# filter2.net
KiCad netlist of a schematic drawn in EAGLE
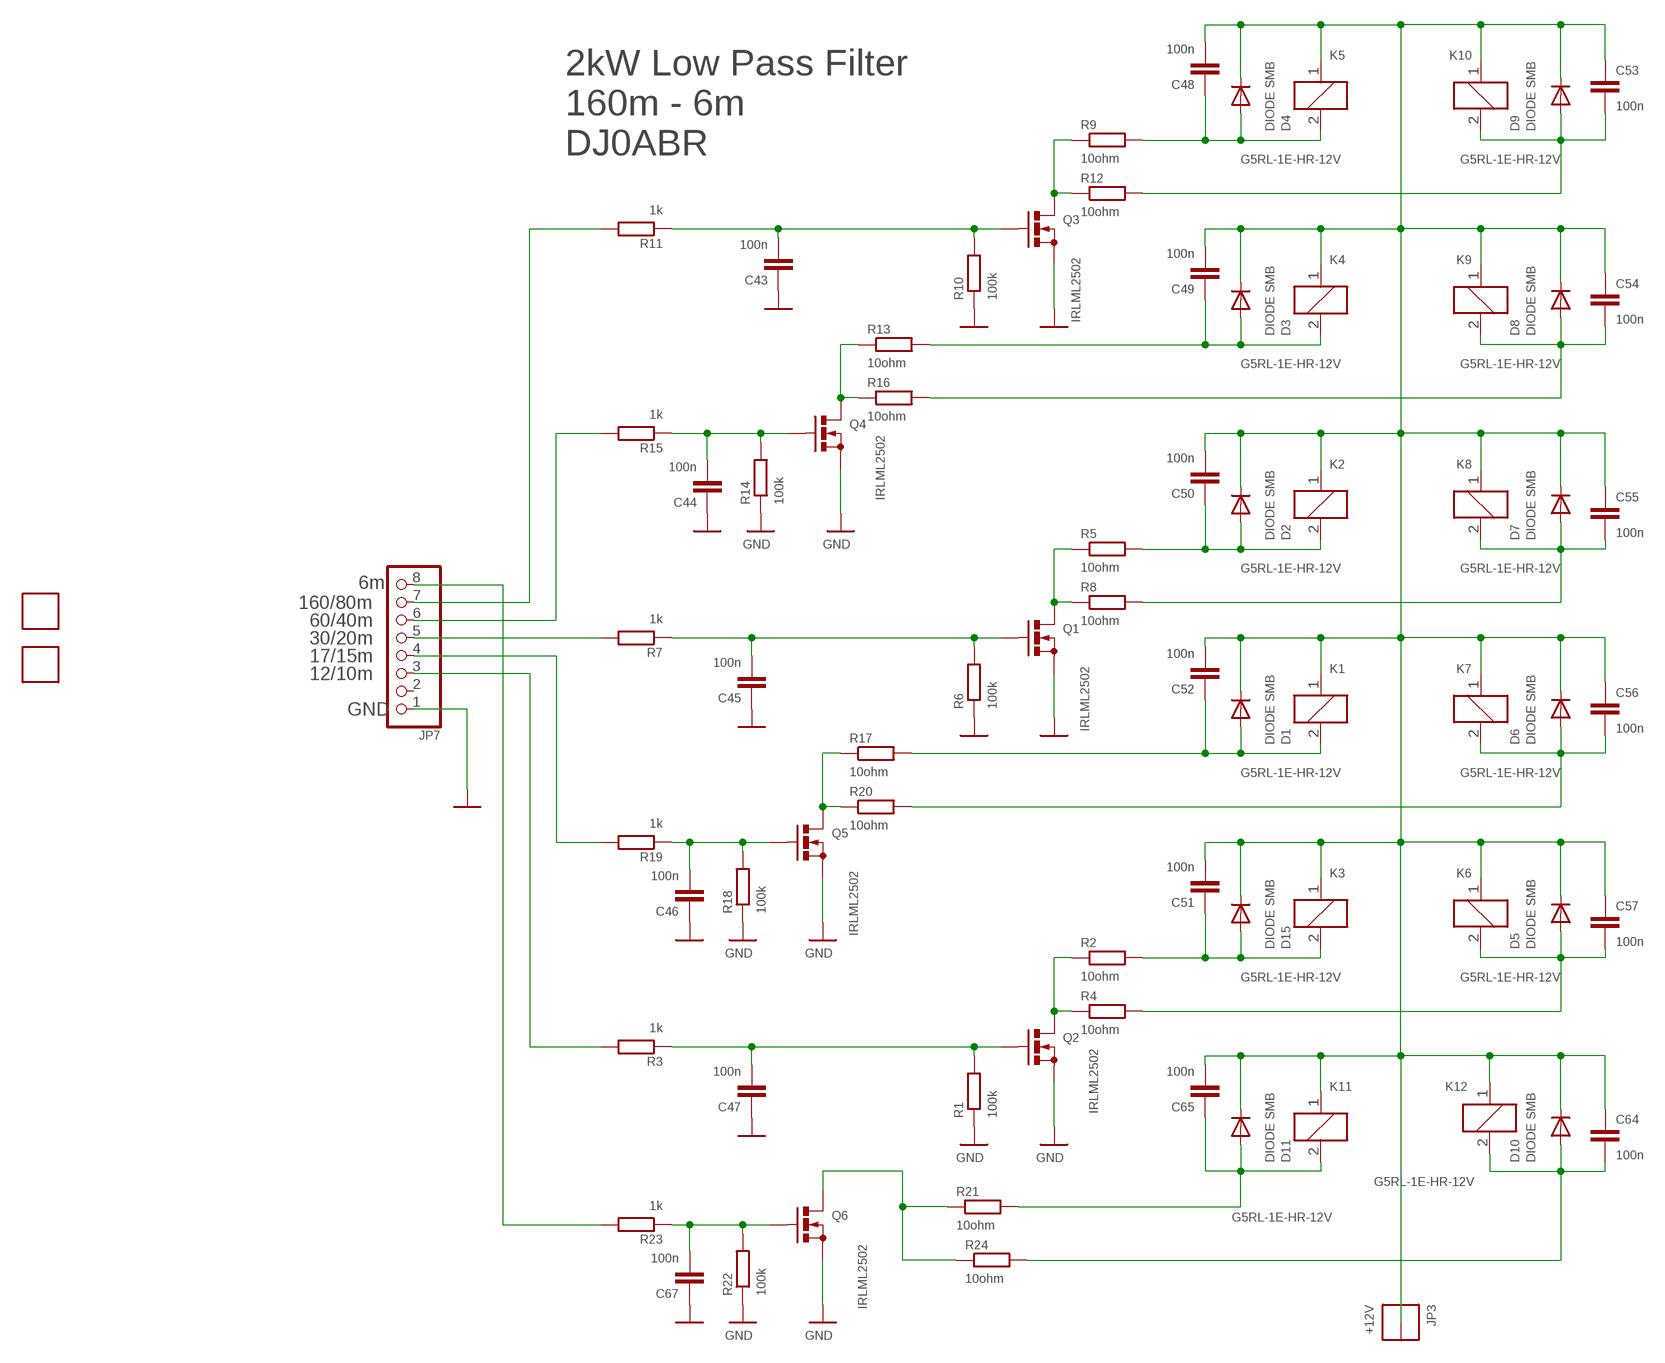
[diagram p0: schematic, sheet 1, part 1 of 2]
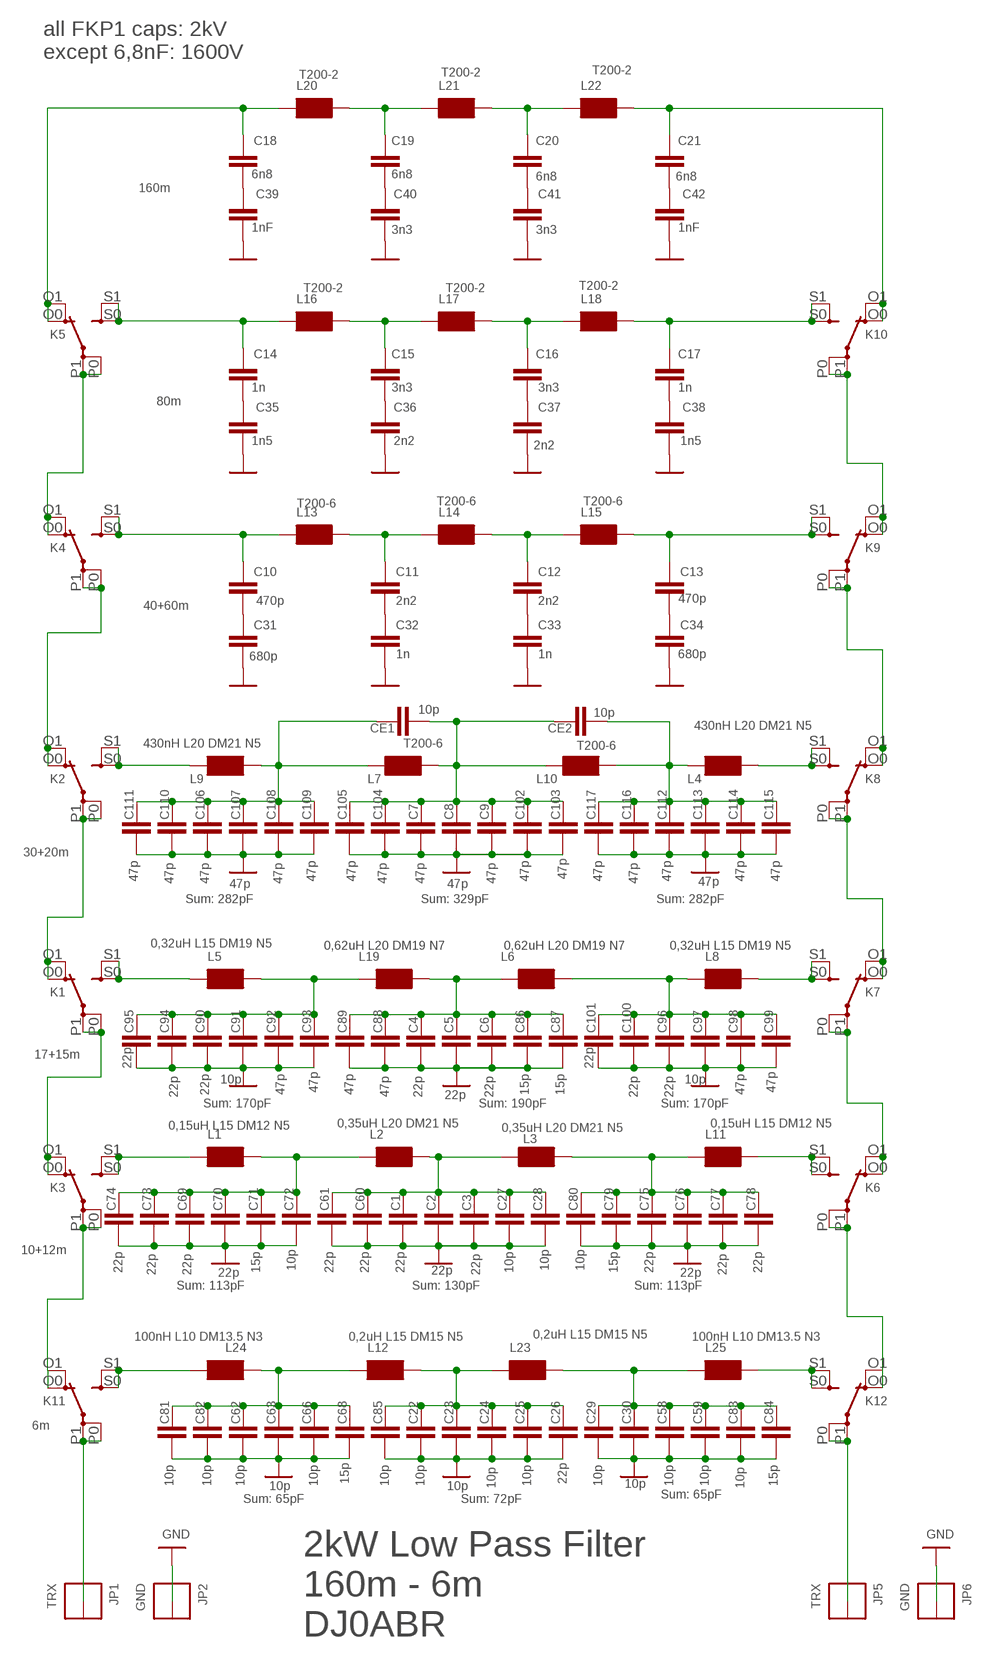
[diagram p1: schematic, sheet 1, part 2 of 2]

(export (version "E")
  (design (tool "Eeschema 10.0.6"))
  (components
    (comp (ref "C1")
      (value "22p")
      (footprint "eagle-import:C1812K")
      (libsource (lib "eagle-import") (part "C-EUC1812K"))
    )
    (comp (ref "C2")
      (value "22p")
      (footprint "eagle-import:C1812K")
      (libsource (lib "eagle-import") (part "C-EUC1812K"))
    )
    (comp (ref "C3")
      (value "22p")
      (footprint "eagle-import:C1812K")
      (libsource (lib "eagle-import") (part "C-EUC1812K"))
    )
    (comp (ref "C4")
      (value "22p")
      (footprint "eagle-import:C1812K")
      (libsource (lib "eagle-import") (part "C-EUC1812K"))
    )
    (comp (ref "C5")
      (value "22p")
      (footprint "eagle-import:C1812K")
      (libsource (lib "eagle-import") (part "C-EUC1812K"))
    )
    (comp (ref "C6")
      (value "22p")
      (footprint "eagle-import:C1812K")
      (libsource (lib "eagle-import") (part "C-EUC1812K"))
    )
    (comp (ref "C7")
      (value "47p")
      (footprint "eagle-import:C1812K")
      (libsource (lib "eagle-import") (part "C-EUC1812K"))
    )
    (comp (ref "C8")
      (value "47p")
      (footprint "eagle-import:C1812K")
      (libsource (lib "eagle-import") (part "C-EUC1812K"))
    )
    (comp (ref "C9")
      (value "47p")
      (footprint "eagle-import:C1812K")
      (libsource (lib "eagle-import") (part "C-EUC1812K"))
    )
    (comp (ref "C10")
      (value "470p")
      (footprint "eagle-import:C150-064X183")
      (libsource (lib "eagle-import") (part "C-EU150-064X183"))
    )
    (comp (ref "C11")
      (value "2n2")
      (footprint "eagle-import:C225-074X268")
      (libsource (lib "eagle-import") (part "C-EU225-074X268"))
    )
    (comp (ref "C12")
      (value "2n2")
      (footprint "eagle-import:C225-074X268")
      (libsource (lib "eagle-import") (part "C-EU225-074X268"))
    )
    (comp (ref "C13")
      (value "470p")
      (footprint "eagle-import:C150-064X183")
      (libsource (lib "eagle-import") (part "C-EU150-064X183"))
    )
    (comp (ref "C14")
      (value "1n")
      (footprint "eagle-import:C225-062X268")
      (libsource (lib "eagle-import") (part "C-EU225-062X268"))
    )
    (comp (ref "C15")
      (value "3n3")
      (footprint "eagle-import:C225-074X268")
      (libsource (lib "eagle-import") (part "C-EU225-074X268"))
    )
    (comp (ref "C16")
      (value "3n3")
      (footprint "eagle-import:C225-074X268")
      (libsource (lib "eagle-import") (part "C-EU225-074X268"))
    )
    (comp (ref "C17")
      (value "1n")
      (footprint "eagle-import:C225-062X268")
      (libsource (lib "eagle-import") (part "C-EU225-062X268"))
    )
    (comp (ref "C18")
      (value "6n8")
      (footprint "eagle-import:C225-074X268")
      (libsource (lib "eagle-import") (part "C-EU225-074X268"))
    )
    (comp (ref "C19")
      (value "6n8")
      (footprint "eagle-import:C225-074X268")
      (libsource (lib "eagle-import") (part "C-EU225-074X268"))
    )
    (comp (ref "C20")
      (value "6n8")
      (footprint "eagle-import:C225-074X268")
      (libsource (lib "eagle-import") (part "C-EU225-074X268"))
    )
    (comp (ref "C21")
      (value "6n8")
      (footprint "eagle-import:C225-074X268")
      (libsource (lib "eagle-import") (part "C-EU225-074X268"))
    )
    (comp (ref "C22")
      (value "10p")
      (footprint "eagle-import:C1812K")
      (libsource (lib "eagle-import") (part "C-EUC1812K"))
    )
    (comp (ref "C23")
      (value "10p")
      (footprint "eagle-import:C1812K")
      (libsource (lib "eagle-import") (part "C-EUC1812K"))
    )
    (comp (ref "C24")
      (value "10p")
      (footprint "eagle-import:C1812K")
      (libsource (lib "eagle-import") (part "C-EUC1812K"))
    )
    (comp (ref "C25")
      (value "10p")
      (footprint "eagle-import:C1812K")
      (libsource (lib "eagle-import") (part "C-EUC1812K"))
    )
    (comp (ref "C26")
      (value "22p")
      (footprint "eagle-import:C1812K")
      (libsource (lib "eagle-import") (part "C-EUC1812K"))
    )
    (comp (ref "C27")
      (value "10p")
      (footprint "eagle-import:C1812K")
      (libsource (lib "eagle-import") (part "C-EUC1812K"))
    )
    (comp (ref "C28")
      (value "10p")
      (footprint "eagle-import:C1812K")
      (libsource (lib "eagle-import") (part "C-EUC1812K"))
    )
    (comp (ref "C29")
      (value "10p")
      (footprint "eagle-import:C1812K")
      (libsource (lib "eagle-import") (part "C-EUC1812K"))
    )
    (comp (ref "C30")
      (value "10p")
      (footprint "eagle-import:C1812K")
      (libsource (lib "eagle-import") (part "C-EUC1812K"))
    )
    (comp (ref "C31")
      (value "680p")
      (footprint "eagle-import:C150-064X183")
      (libsource (lib "eagle-import") (part "C-EU150-064X183"))
    )
    (comp (ref "C32")
      (value "1n")
      (footprint "eagle-import:C225-062X268")
      (libsource (lib "eagle-import") (part "C-EU225-062X268"))
    )
    (comp (ref "C33")
      (value "1n")
      (footprint "eagle-import:C225-062X268")
      (libsource (lib "eagle-import") (part "C-EU225-062X268"))
    )
    (comp (ref "C34")
      (value "680p")
      (footprint "eagle-import:C150-064X183")
      (libsource (lib "eagle-import") (part "C-EU150-064X183"))
    )
    (comp (ref "C35")
      (value "1n5")
      (footprint "eagle-import:C225-074X268")
      (libsource (lib "eagle-import") (part "C-EU225-074X268"))
    )
    (comp (ref "C36")
      (value "2n2")
      (footprint "eagle-import:C225-074X268")
      (libsource (lib "eagle-import") (part "C-EU225-074X268"))
    )
    (comp (ref "C37")
      (value "2n2")
      (footprint "eagle-import:C225-074X268")
      (libsource (lib "eagle-import") (part "C-EU225-074X268"))
    )
    (comp (ref "C38")
      (value "1n5")
      (footprint "eagle-import:C225-074X268")
      (libsource (lib "eagle-import") (part "C-EU225-074X268"))
    )
    (comp (ref "C39")
      (value "1nF")
      (footprint "eagle-import:C225-074X268")
      (libsource (lib "eagle-import") (part "C-EU225-074X268"))
    )
    (comp (ref "C40")
      (value "3n3")
      (footprint "eagle-import:C225-087X268")
      (libsource (lib "eagle-import") (part "C-EU225-087X268"))
    )
    (comp (ref "C41")
      (value "3n3")
      (footprint "eagle-import:C225-087X268")
      (libsource (lib "eagle-import") (part "C-EU225-087X268"))
    )
    (comp (ref "C42")
      (value "1nF")
      (footprint "eagle-import:C225-074X268")
      (libsource (lib "eagle-import") (part "C-EU225-074X268"))
    )
    (comp (ref "C43")
      (value "100n")
      (footprint "eagle-import:C0603K")
      (libsource (lib "eagle-import") (part "C-EUC0603K"))
    )
    (comp (ref "C44")
      (value "100n")
      (footprint "eagle-import:C0603K")
      (libsource (lib "eagle-import") (part "C-EUC0603K"))
    )
    (comp (ref "C45")
      (value "100n")
      (footprint "eagle-import:C0603K")
      (libsource (lib "eagle-import") (part "C-EUC0603K"))
    )
    (comp (ref "C46")
      (value "100n")
      (footprint "eagle-import:C0603K")
      (libsource (lib "eagle-import") (part "C-EUC0603K"))
    )
    (comp (ref "C47")
      (value "100n")
      (footprint "eagle-import:C0603K")
      (libsource (lib "eagle-import") (part "C-EUC0603K"))
    )
    (comp (ref "C48")
      (value "100n")
      (footprint "eagle-import:C0603K")
      (libsource (lib "eagle-import") (part "C-EUC0603K"))
    )
    (comp (ref "C49")
      (value "100n")
      (footprint "eagle-import:C0603K")
      (libsource (lib "eagle-import") (part "C-EUC0603K"))
    )
    (comp (ref "C50")
      (value "100n")
      (footprint "eagle-import:C0603K")
      (libsource (lib "eagle-import") (part "C-EUC0603K"))
    )
    (comp (ref "C51")
      (value "100n")
      (footprint "eagle-import:C0603K")
      (libsource (lib "eagle-import") (part "C-EUC0603K"))
    )
    (comp (ref "C52")
      (value "100n")
      (footprint "eagle-import:C0603K")
      (libsource (lib "eagle-import") (part "C-EUC0603K"))
    )
    (comp (ref "C53")
      (value "100n")
      (footprint "eagle-import:C0603K")
      (libsource (lib "eagle-import") (part "C-EUC0603K"))
    )
    (comp (ref "C54")
      (value "100n")
      (footprint "eagle-import:C0603K")
      (libsource (lib "eagle-import") (part "C-EUC0603K"))
    )
    (comp (ref "C55")
      (value "100n")
      (footprint "eagle-import:C0603K")
      (libsource (lib "eagle-import") (part "C-EUC0603K"))
    )
    (comp (ref "C56")
      (value "100n")
      (footprint "eagle-import:C0603K")
      (libsource (lib "eagle-import") (part "C-EUC0603K"))
    )
    (comp (ref "C57")
      (value "100n")
      (footprint "eagle-import:C0603K")
      (libsource (lib "eagle-import") (part "C-EUC0603K"))
    )
    (comp (ref "C58")
      (value "10p")
      (footprint "eagle-import:C1812K")
      (libsource (lib "eagle-import") (part "C-EUC1812K"))
    )
    (comp (ref "C59")
      (value "10p")
      (footprint "eagle-import:C1812K")
      (libsource (lib "eagle-import") (part "C-EUC1812K"))
    )
    (comp (ref "C60")
      (value "22p")
      (footprint "eagle-import:C1812K")
      (libsource (lib "eagle-import") (part "C-EUC1812K"))
    )
    (comp (ref "C61")
      (value "22p")
      (footprint "eagle-import:C1812K")
      (libsource (lib "eagle-import") (part "C-EUC1812K"))
    )
    (comp (ref "C62")
      (value "10p")
      (footprint "eagle-import:C1812K")
      (libsource (lib "eagle-import") (part "C-EUC1812K"))
    )
    (comp (ref "C63")
      (value "10p")
      (footprint "eagle-import:C1812K")
      (libsource (lib "eagle-import") (part "C-EUC1812K"))
    )
    (comp (ref "C64")
      (value "100n")
      (footprint "eagle-import:C0603K")
      (libsource (lib "eagle-import") (part "C-EUC0603K"))
    )
    (comp (ref "C65")
      (value "100n")
      (footprint "eagle-import:C0603K")
      (libsource (lib "eagle-import") (part "C-EUC0603K"))
    )
    (comp (ref "C66")
      (value "10p")
      (footprint "eagle-import:C1812K")
      (libsource (lib "eagle-import") (part "C-EUC1812K"))
    )
    (comp (ref "C67")
      (value "100n")
      (footprint "eagle-import:C0603K")
      (libsource (lib "eagle-import") (part "C-EUC0603K"))
    )
    (comp (ref "C68")
      (value "15p")
      (footprint "eagle-import:C1812K")
      (libsource (lib "eagle-import") (part "C-EUC1812K"))
    )
    (comp (ref "C69")
      (value "22p")
      (footprint "eagle-import:C1812K")
      (libsource (lib "eagle-import") (part "C-EUC1812K"))
    )
    (comp (ref "C70")
      (value "22p")
      (footprint "eagle-import:C1812K")
      (libsource (lib "eagle-import") (part "C-EUC1812K"))
    )
    (comp (ref "C71")
      (value "15p")
      (footprint "eagle-import:C1812K")
      (libsource (lib "eagle-import") (part "C-EUC1812K"))
    )
    (comp (ref "C72")
      (value "10p")
      (footprint "eagle-import:C1812K")
      (libsource (lib "eagle-import") (part "C-EUC1812K"))
    )
    (comp (ref "C73")
      (value "22p")
      (footprint "eagle-import:C1812K")
      (libsource (lib "eagle-import") (part "C-EUC1812K"))
    )
    (comp (ref "C74")
      (value "22p")
      (footprint "eagle-import:C1812K")
      (libsource (lib "eagle-import") (part "C-EUC1812K"))
    )
    (comp (ref "C75")
      (value "22p")
      (footprint "eagle-import:C1812K")
      (libsource (lib "eagle-import") (part "C-EUC1812K"))
    )
    (comp (ref "C76")
      (value "22p")
      (footprint "eagle-import:C1812K")
      (libsource (lib "eagle-import") (part "C-EUC1812K"))
    )
    (comp (ref "C77")
      (value "22p")
      (footprint "eagle-import:C1812K")
      (libsource (lib "eagle-import") (part "C-EUC1812K"))
    )
    (comp (ref "C78")
      (value "22p")
      (footprint "eagle-import:C1812K")
      (libsource (lib "eagle-import") (part "C-EUC1812K"))
    )
    (comp (ref "C79")
      (value "15p")
      (footprint "eagle-import:C1812K")
      (libsource (lib "eagle-import") (part "C-EUC1812K"))
    )
    (comp (ref "C80")
      (value "10p")
      (footprint "eagle-import:C1812K")
      (libsource (lib "eagle-import") (part "C-EUC1812K"))
    )
    (comp (ref "C81")
      (value "10p")
      (footprint "eagle-import:C1812K")
      (libsource (lib "eagle-import") (part "C-EUC1812K"))
    )
    (comp (ref "C82")
      (value "10p")
      (footprint "eagle-import:C1812K")
      (libsource (lib "eagle-import") (part "C-EUC1812K"))
    )
    (comp (ref "C83")
      (value "10p")
      (footprint "eagle-import:C1812K")
      (libsource (lib "eagle-import") (part "C-EUC1812K"))
    )
    (comp (ref "C84")
      (value "15p")
      (footprint "eagle-import:C1812K")
      (libsource (lib "eagle-import") (part "C-EUC1812K"))
    )
    (comp (ref "C85")
      (value "10p")
      (footprint "eagle-import:C1812K")
      (libsource (lib "eagle-import") (part "C-EUC1812K"))
    )
    (comp (ref "C86")
      (value "15p")
      (footprint "eagle-import:C1812K")
      (libsource (lib "eagle-import") (part "C-EUC1812K"))
    )
    (comp (ref "C87")
      (value "15p")
      (footprint "eagle-import:C1812K")
      (libsource (lib "eagle-import") (part "C-EUC1812K"))
    )
    (comp (ref "C88")
      (value "47p")
      (footprint "eagle-import:C1812K")
      (libsource (lib "eagle-import") (part "C-EUC1812K"))
    )
    (comp (ref "C89")
      (value "47p")
      (footprint "eagle-import:C1812K")
      (libsource (lib "eagle-import") (part "C-EUC1812K"))
    )
    (comp (ref "C90")
      (value "22p")
      (footprint "eagle-import:C1812K")
      (libsource (lib "eagle-import") (part "C-EUC1812K"))
    )
    (comp (ref "C91")
      (value "10p")
      (footprint "eagle-import:C1812K")
      (libsource (lib "eagle-import") (part "C-EUC1812K"))
    )
    (comp (ref "C92")
      (value "47p")
      (footprint "eagle-import:C1812K")
      (libsource (lib "eagle-import") (part "C-EUC1812K"))
    )
    (comp (ref "C93")
      (value "47p")
      (footprint "eagle-import:C1812K")
      (libsource (lib "eagle-import") (part "C-EUC1812K"))
    )
    (comp (ref "C94")
      (value "22p")
      (footprint "eagle-import:C1812K")
      (libsource (lib "eagle-import") (part "C-EUC1812K"))
    )
    (comp (ref "C95")
      (value "22p")
      (footprint "eagle-import:C1812K")
      (libsource (lib "eagle-import") (part "C-EUC1812K"))
    )
    (comp (ref "C96")
      (value "22p")
      (footprint "eagle-import:C1812K")
      (libsource (lib "eagle-import") (part "C-EUC1812K"))
    )
    (comp (ref "C97")
      (value "10p")
      (footprint "eagle-import:C1812K")
      (libsource (lib "eagle-import") (part "C-EUC1812K"))
    )
    (comp (ref "C98")
      (value "47p")
      (footprint "eagle-import:C1812K")
      (libsource (lib "eagle-import") (part "C-EUC1812K"))
    )
    (comp (ref "C99")
      (value "47p")
      (footprint "eagle-import:C1812K")
      (libsource (lib "eagle-import") (part "C-EUC1812K"))
    )
    (comp (ref "C100")
      (value "22p")
      (footprint "eagle-import:C1812K")
      (libsource (lib "eagle-import") (part "C-EUC1812K"))
    )
    (comp (ref "C101")
      (value "22p")
      (footprint "eagle-import:C1812K")
      (libsource (lib "eagle-import") (part "C-EUC1812K"))
    )
    (comp (ref "C102")
      (value "47p")
      (footprint "eagle-import:C1812K")
      (libsource (lib "eagle-import") (part "C-EUC1812K"))
    )
    (comp (ref "C103")
      (value "47p")
      (footprint "eagle-import:C1812K")
      (libsource (lib "eagle-import") (part "C-EUC1812K"))
    )
    (comp (ref "C104")
      (value "47p")
      (footprint "eagle-import:C1812K")
      (libsource (lib "eagle-import") (part "C-EUC1812K"))
    )
    (comp (ref "C105")
      (value "47p")
      (footprint "eagle-import:C1812K")
      (libsource (lib "eagle-import") (part "C-EUC1812K"))
    )
    (comp (ref "C106")
      (value "47p")
      (footprint "eagle-import:C1812K")
      (libsource (lib "eagle-import") (part "C-EUC1812K"))
    )
    (comp (ref "C107")
      (value "47p")
      (footprint "eagle-import:C1812K")
      (libsource (lib "eagle-import") (part "C-EUC1812K"))
    )
    (comp (ref "C108")
      (value "47p")
      (footprint "eagle-import:C1812K")
      (libsource (lib "eagle-import") (part "C-EUC1812K"))
    )
    (comp (ref "C109")
      (value "47p")
      (footprint "eagle-import:C1812K")
      (libsource (lib "eagle-import") (part "C-EUC1812K"))
    )
    (comp (ref "C110")
      (value "47p")
      (footprint "eagle-import:C1812K")
      (libsource (lib "eagle-import") (part "C-EUC1812K"))
    )
    (comp (ref "C111")
      (value "47p")
      (footprint "eagle-import:C1812K")
      (libsource (lib "eagle-import") (part "C-EUC1812K"))
    )
    (comp (ref "C112")
      (value "47p")
      (footprint "eagle-import:C1812K")
      (libsource (lib "eagle-import") (part "C-EUC1812K"))
    )
    (comp (ref "C113")
      (value "47p")
      (footprint "eagle-import:C1812K")
      (libsource (lib "eagle-import") (part "C-EUC1812K"))
    )
    (comp (ref "C114")
      (value "47p")
      (footprint "eagle-import:C1812K")
      (libsource (lib "eagle-import") (part "C-EUC1812K"))
    )
    (comp (ref "C115")
      (value "47p")
      (footprint "eagle-import:C1812K")
      (libsource (lib "eagle-import") (part "C-EUC1812K"))
    )
    (comp (ref "C116")
      (value "47p")
      (footprint "eagle-import:C1812K")
      (libsource (lib "eagle-import") (part "C-EUC1812K"))
    )
    (comp (ref "C117")
      (value "47p")
      (footprint "eagle-import:C1812K")
      (libsource (lib "eagle-import") (part "C-EUC1812K"))
    )
    (comp (ref "CE1")
      (value "10p")
      (footprint "eagle-import:C1812K")
      (libsource (lib "eagle-import") (part "C-EUC1812K"))
    )
    (comp (ref "CE2")
      (value "10p")
      (footprint "eagle-import:C1812K")
      (libsource (lib "eagle-import") (part "C-EUC1812K"))
    )
    (comp (ref "D1")
      (value "DIODE SMB")
      (footprint "eagle-import:SMB")
      (libsource (lib "eagle-import") (part "DIODE-SMB"))
    )
    (comp (ref "D2")
      (value "DIODE SMB")
      (footprint "eagle-import:SMB")
      (libsource (lib "eagle-import") (part "DIODE-SMB"))
    )
    (comp (ref "D3")
      (value "DIODE SMB")
      (footprint "eagle-import:SMB")
      (libsource (lib "eagle-import") (part "DIODE-SMB"))
    )
    (comp (ref "D4")
      (value "DIODE SMB")
      (footprint "eagle-import:SMB")
      (libsource (lib "eagle-import") (part "DIODE-SMB"))
    )
    (comp (ref "D5")
      (value "DIODE SMB")
      (footprint "eagle-import:SMB")
      (libsource (lib "eagle-import") (part "DIODE-SMB"))
    )
    (comp (ref "D6")
      (value "DIODE SMB")
      (footprint "eagle-import:SMB")
      (libsource (lib "eagle-import") (part "DIODE-SMB"))
    )
    (comp (ref "D7")
      (value "DIODE SMB")
      (footprint "eagle-import:SMB")
      (libsource (lib "eagle-import") (part "DIODE-SMB"))
    )
    (comp (ref "D8")
      (value "DIODE SMB")
      (footprint "eagle-import:SMB")
      (libsource (lib "eagle-import") (part "DIODE-SMB"))
    )
    (comp (ref "D9")
      (value "DIODE SMB")
      (footprint "eagle-import:SMB")
      (libsource (lib "eagle-import") (part "DIODE-SMB"))
    )
    (comp (ref "D10")
      (value "DIODE SMB")
      (footprint "eagle-import:SMB")
      (libsource (lib "eagle-import") (part "DIODE-SMB"))
    )
    (comp (ref "D11")
      (value "DIODE SMB")
      (footprint "eagle-import:SMB")
      (libsource (lib "eagle-import") (part "DIODE-SMB"))
    )
    (comp (ref "D15")
      (value "DIODE SMB")
      (footprint "eagle-import:SMB")
      (libsource (lib "eagle-import") (part "DIODE-SMB"))
    )
    (comp (ref "FID1")
      (value "FIDUCIAL")
      (footprint "eagle-import:FIDUCIAL")
      (libsource (lib "eagle-import") (part "FIDUCIAL"))
    )
    (comp (ref "FID2")
      (value "FIDUCIAL")
      (footprint "eagle-import:FIDUCIAL")
      (libsource (lib "eagle-import") (part "FIDUCIAL"))
    )
    (comp (ref "JP1")
      (value "TRX")
      (footprint "eagle-import:THICKPIN")
      (libsource (lib "eagle-import") (part "THICKPINSQUARE"))
    )
    (comp (ref "JP2")
      (value "GND")
      (footprint "eagle-import:THICKPIN")
      (libsource (lib "eagle-import") (part "THICKPINSQUARE"))
    )
    (comp (ref "JP3")
      (value "+12V")
      (footprint "eagle-import:THICKPIN")
      (libsource (lib "eagle-import") (part "THICKPINSQUARE"))
    )
    (comp (ref "JP5")
      (value "TRX")
      (footprint "eagle-import:THICKPIN")
      (libsource (lib "eagle-import") (part "THICKPINSQUARE"))
    )
    (comp (ref "JP6")
      (value "GND")
      (footprint "eagle-import:THICKPIN")
      (libsource (lib "eagle-import") (part "THICKPINSQUARE"))
    )
    (comp (ref "JP7")
      (value "PINHD-1X8")
      (footprint "eagle-import:1X08")
      (libsource (lib "eagle-import") (part "PINHD-1X8"))
    )
    (comp (ref "K1")
      (value "G5RL-1E-HR-12V")
      (footprint "eagle-import:G2RE")
      (libsource (lib "eagle-import") (part "G2RE"))
    )
    (comp (ref "K2")
      (value "G5RL-1E-HR-12V")
      (footprint "eagle-import:G2RE")
      (libsource (lib "eagle-import") (part "G2RE"))
    )
    (comp (ref "K3")
      (value "G5RL-1E-HR-12V")
      (footprint "eagle-import:G2RE")
      (libsource (lib "eagle-import") (part "G2RE"))
    )
    (comp (ref "K4")
      (value "G5RL-1E-HR-12V")
      (footprint "eagle-import:G2RE")
      (libsource (lib "eagle-import") (part "G2RE"))
    )
    (comp (ref "K5")
      (value "G5RL-1E-HR-12V")
      (footprint "eagle-import:G2RE")
      (libsource (lib "eagle-import") (part "G2RE"))
    )
    (comp (ref "K6")
      (value "G5RL-1E-HR-12V")
      (footprint "eagle-import:G2RE")
      (libsource (lib "eagle-import") (part "G2RE"))
    )
    (comp (ref "K7")
      (value "G5RL-1E-HR-12V")
      (footprint "eagle-import:G2RE")
      (libsource (lib "eagle-import") (part "G2RE"))
    )
    (comp (ref "K8")
      (value "G5RL-1E-HR-12V")
      (footprint "eagle-import:G2RE")
      (libsource (lib "eagle-import") (part "G2RE"))
    )
    (comp (ref "K9")
      (value "G5RL-1E-HR-12V")
      (footprint "eagle-import:G2RE")
      (libsource (lib "eagle-import") (part "G2RE"))
    )
    (comp (ref "K10")
      (value "G5RL-1E-HR-12V")
      (footprint "eagle-import:G2RE")
      (libsource (lib "eagle-import") (part "G2RE"))
    )
    (comp (ref "K11")
      (value "G5RL-1E-HR-12V")
      (footprint "eagle-import:G2RE")
      (libsource (lib "eagle-import") (part "G2RE"))
    )
    (comp (ref "K12")
      (value "G5RL-1E-HR-12V")
      (footprint "eagle-import:G2RE")
      (libsource (lib "eagle-import") (part "G2RE"))
    )
    (comp (ref "L1")
      (value "0,15uH L15 DM12 N5")
      (footprint "eagle-import:LUFTSPULE_L15XDM14")
      (libsource (lib "eagle-import") (part "LL15X14"))
    )
    (comp (ref "L2")
      (value "0,35uH L20 DM21 N5")
      (footprint "eagle-import:LUFTSPULE_L17XDM20")
      (libsource (lib "eagle-import") (part "LL17X20"))
    )
    (comp (ref "L3")
      (value "0,35uH L20 DM21 N5")
      (footprint "eagle-import:LUFTSPULE_L17XDM20")
      (libsource (lib "eagle-import") (part "LL17X20"))
    )
    (comp (ref "L4")
      (value "430nH L20 DM21 N5")
      (footprint "eagle-import:LUFTSPULE_20X20RM20")
      (libsource (lib "eagle-import") (part "L20X20"))
    )
    (comp (ref "L5")
      (value "0,32uH L15 DM19 N5")
      (footprint "eagle-import:LUFTSPULR_L15XDM20")
      (libsource (lib "eagle-import") (part "LL15X20"))
    )
    (comp (ref "L6")
      (value "0,62uH L20 DM19 N7")
      (footprint "eagle-import:LUFTSPULE_20X20RM20")
      (libsource (lib "eagle-import") (part "L20X20"))
    )
    (comp (ref "L7")
      (value "T200-6")
      (footprint "eagle-import:KERN200_STEHEND_2PIN")
      (libsource (lib "eagle-import") (part "LT200"))
    )
    (comp (ref "L8")
      (value "0,32uH L15 DM19 N5")
      (footprint "eagle-import:LUFTSPULR_L15XDM20")
      (libsource (lib "eagle-import") (part "LL15X20"))
    )
    (comp (ref "L9")
      (value "430nH L20 DM21 N5")
      (footprint "eagle-import:LUFTSPULE_20X20RM20")
      (libsource (lib "eagle-import") (part "L20X20"))
    )
    (comp (ref "L10")
      (value "T200-6")
      (footprint "eagle-import:KERN200_STEHEND_2PIN")
      (libsource (lib "eagle-import") (part "LT200"))
    )
    (comp (ref "L11")
      (value "0,15uH L15 DM12 N5")
      (footprint "eagle-import:LUFTSPULE_L15XDM14")
      (libsource (lib "eagle-import") (part "LL15X14"))
    )
    (comp (ref "L12")
      (value "0,2uH L15 DM15 N5")
      (footprint "eagle-import:LUFTSPULE_L15XDM14")
      (libsource (lib "eagle-import") (part "LL15X14"))
    )
    (comp (ref "L13")
      (value "T200-6")
      (footprint "eagle-import:KERN200_STEHEND_2PIN")
      (libsource (lib "eagle-import") (part "LT200"))
    )
    (comp (ref "L14")
      (value "T200-6")
      (footprint "eagle-import:KERN200_STEHEND_2PIN")
      (libsource (lib "eagle-import") (part "LT200"))
    )
    (comp (ref "L15")
      (value "T200-6")
      (footprint "eagle-import:KERN200_STEHEND_2PIN")
      (libsource (lib "eagle-import") (part "LT200"))
    )
    (comp (ref "L16")
      (value "T200-2")
      (footprint "eagle-import:KERN200_STEHEND_2PIN")
      (libsource (lib "eagle-import") (part "LT200"))
    )
    (comp (ref "L17")
      (value "T200-2")
      (footprint "eagle-import:KERN200_STEHEND_2PIN")
      (libsource (lib "eagle-import") (part "LT200"))
    )
    (comp (ref "L18")
      (value "T200-2")
      (footprint "eagle-import:KERN200_STEHEND_2PIN")
      (libsource (lib "eagle-import") (part "LT200"))
    )
    (comp (ref "L19")
      (value "0,62uH L20 DM19 N7")
      (footprint "eagle-import:LUFTSPULE_20X20RM20")
      (libsource (lib "eagle-import") (part "L20X20"))
    )
    (comp (ref "L20")
      (value "T200-2")
      (footprint "eagle-import:KERN200_STEHEND_2PIN")
      (libsource (lib "eagle-import") (part "LT200"))
    )
    (comp (ref "L21")
      (value "T200-2")
      (footprint "eagle-import:KERN200_STEHEND_2PIN")
      (libsource (lib "eagle-import") (part "LT200"))
    )
    (comp (ref "L22")
      (value "T200-2")
      (footprint "eagle-import:KERN200_STEHEND_2PIN")
      (libsource (lib "eagle-import") (part "LT200"))
    )
    (comp (ref "L23")
      (value "0,2uH L15 DM15 N5")
      (footprint "eagle-import:LUFTSPULE_L15XDM14")
      (libsource (lib "eagle-import") (part "LL15X14"))
    )
    (comp (ref "L24")
      (value "100nH L10 DM13.5 N3")
      (footprint "eagle-import:LUFTSPULE_10X13K5")
      (libsource (lib "eagle-import") (part "L"))
    )
    (comp (ref "L25")
      (value "100nH L10 DM13.5 N3")
      (footprint "eagle-import:LUFTSPULE_10X13K5")
      (libsource (lib "eagle-import") (part "L"))
    )
    (comp (ref "Q1")
      (value "IRLML2502")
      (footprint "eagle-import:SOT23")
      (libsource (lib "eagle-import") (part "BS170_SMD"))
    )
    (comp (ref "Q2")
      (value "IRLML2502")
      (footprint "eagle-import:SOT23")
      (libsource (lib "eagle-import") (part "BS170_SMD"))
    )
    (comp (ref "Q3")
      (value "IRLML2502")
      (footprint "eagle-import:SOT23")
      (libsource (lib "eagle-import") (part "BS170_SMD"))
    )
    (comp (ref "Q4")
      (value "IRLML2502")
      (footprint "eagle-import:SOT23")
      (libsource (lib "eagle-import") (part "BS170_SMD"))
    )
    (comp (ref "Q5")
      (value "IRLML2502")
      (footprint "eagle-import:SOT23")
      (libsource (lib "eagle-import") (part "BS170_SMD"))
    )
    (comp (ref "Q6")
      (value "IRLML2502")
      (footprint "eagle-import:SOT23")
      (libsource (lib "eagle-import") (part "BS170_SMD"))
    )
    (comp (ref "R1")
      (value "100k")
      (footprint "eagle-import:R0603")
      (libsource (lib "eagle-import") (part "R-EU_R0603"))
    )
    (comp (ref "R2")
      (value "10ohm")
      (footprint "eagle-import:R0603")
      (libsource (lib "eagle-import") (part "R-EU_R0603"))
    )
    (comp (ref "R3")
      (value "1k")
      (footprint "eagle-import:R0603")
      (libsource (lib "eagle-import") (part "R-EU_R0603"))
    )
    (comp (ref "R4")
      (value "10ohm")
      (footprint "eagle-import:R0603")
      (libsource (lib "eagle-import") (part "R-EU_R0603"))
    )
    (comp (ref "R5")
      (value "10ohm")
      (footprint "eagle-import:R0603")
      (libsource (lib "eagle-import") (part "R-EU_R0603"))
    )
    (comp (ref "R6")
      (value "100k")
      (footprint "eagle-import:R0603")
      (libsource (lib "eagle-import") (part "R-EU_R0603"))
    )
    (comp (ref "R7")
      (value "1k")
      (footprint "eagle-import:R0603")
      (libsource (lib "eagle-import") (part "R-EU_R0603"))
    )
    (comp (ref "R8")
      (value "10ohm")
      (footprint "eagle-import:R0603")
      (libsource (lib "eagle-import") (part "R-EU_R0603"))
    )
    (comp (ref "R9")
      (value "10ohm")
      (footprint "eagle-import:R0603")
      (libsource (lib "eagle-import") (part "R-EU_R0603"))
    )
    (comp (ref "R10")
      (value "100k")
      (footprint "eagle-import:R0603")
      (libsource (lib "eagle-import") (part "R-EU_R0603"))
    )
    (comp (ref "R11")
      (value "1k")
      (footprint "eagle-import:R0603")
      (libsource (lib "eagle-import") (part "R-EU_R0603"))
    )
    (comp (ref "R12")
      (value "10ohm")
      (footprint "eagle-import:R0603")
      (libsource (lib "eagle-import") (part "R-EU_R0603"))
    )
    (comp (ref "R13")
      (value "10ohm")
      (footprint "eagle-import:R0603")
      (libsource (lib "eagle-import") (part "R-EU_R0603"))
    )
    (comp (ref "R14")
      (value "100k")
      (footprint "eagle-import:R0603")
      (libsource (lib "eagle-import") (part "R-EU_R0603"))
    )
    (comp (ref "R15")
      (value "1k")
      (footprint "eagle-import:R0603")
      (libsource (lib "eagle-import") (part "R-EU_R0603"))
    )
    (comp (ref "R16")
      (value "10ohm")
      (footprint "eagle-import:R0603")
      (libsource (lib "eagle-import") (part "R-EU_R0603"))
    )
    (comp (ref "R17")
      (value "10ohm")
      (footprint "eagle-import:R0603")
      (libsource (lib "eagle-import") (part "R-EU_R0603"))
    )
    (comp (ref "R18")
      (value "100k")
      (footprint "eagle-import:R0603")
      (libsource (lib "eagle-import") (part "R-EU_R0603"))
    )
    (comp (ref "R19")
      (value "1k")
      (footprint "eagle-import:R0603")
      (libsource (lib "eagle-import") (part "R-EU_R0603"))
    )
    (comp (ref "R20")
      (value "10ohm")
      (footprint "eagle-import:R0603")
      (libsource (lib "eagle-import") (part "R-EU_R0603"))
    )
    (comp (ref "R21")
      (value "10ohm")
      (footprint "eagle-import:R0603")
      (libsource (lib "eagle-import") (part "R-EU_R0603"))
    )
    (comp (ref "R22")
      (value "100k")
      (footprint "eagle-import:R0603")
      (libsource (lib "eagle-import") (part "R-EU_R0603"))
    )
    (comp (ref "R23")
      (value "1k")
      (footprint "eagle-import:R0603")
      (libsource (lib "eagle-import") (part "R-EU_R0603"))
    )
    (comp (ref "R24")
      (value "10ohm")
      (footprint "eagle-import:R0603")
      (libsource (lib "eagle-import") (part "R-EU_R0603"))
    )
  )
  (nets
    (net (code "1") (name "GND") (class "Default")
      (node (ref "C1") (pin "2") (pinfunction "2_2") (pintype "passive"))
      (node (ref "C100") (pin "2") (pinfunction "2_2") (pintype "passive"))
      (node (ref "C101") (pin "2") (pinfunction "2_2") (pintype "passive"))
      (node (ref "C102") (pin "2") (pinfunction "2_2") (pintype "passive"))
      (node (ref "C103") (pin "2") (pinfunction "2_2") (pintype "passive"))
      (node (ref "C104") (pin "2") (pinfunction "2_2") (pintype "passive"))
      (node (ref "C105") (pin "2") (pinfunction "2_2") (pintype "passive"))
      (node (ref "C106") (pin "2") (pinfunction "2_2") (pintype "passive"))
      (node (ref "C107") (pin "2") (pinfunction "2_2") (pintype "passive"))
      (node (ref "C108") (pin "2") (pinfunction "2_2") (pintype "passive"))
      (node (ref "C109") (pin "2") (pinfunction "2_2") (pintype "passive"))
      (node (ref "C110") (pin "2") (pinfunction "2_2") (pintype "passive"))
      (node (ref "C111") (pin "2") (pinfunction "2_2") (pintype "passive"))
      (node (ref "C112") (pin "2") (pinfunction "2_2") (pintype "passive"))
      (node (ref "C113") (pin "2") (pinfunction "2_2") (pintype "passive"))
      (node (ref "C114") (pin "2") (pinfunction "2_2") (pintype "passive"))
      (node (ref "C115") (pin "2") (pinfunction "2_2") (pintype "passive"))
      (node (ref "C116") (pin "2") (pinfunction "2_2") (pintype "passive"))
      (node (ref "C117") (pin "2") (pinfunction "2_2") (pintype "passive"))
      (node (ref "C2") (pin "2") (pinfunction "2_2") (pintype "passive"))
      (node (ref "C22") (pin "2") (pinfunction "2_2") (pintype "passive"))
      (node (ref "C23") (pin "2") (pinfunction "2_2") (pintype "passive"))
      (node (ref "C24") (pin "2") (pinfunction "2_2") (pintype "passive"))
      (node (ref "C25") (pin "2") (pinfunction "2_2") (pintype "passive"))
      (node (ref "C26") (pin "2") (pinfunction "2_2") (pintype "passive"))
      (node (ref "C27") (pin "2") (pinfunction "2_2") (pintype "passive"))
      (node (ref "C28") (pin "2") (pinfunction "2_2") (pintype "passive"))
      (node (ref "C29") (pin "2") (pinfunction "2_2") (pintype "passive"))
      (node (ref "C3") (pin "2") (pinfunction "2_2") (pintype "passive"))
      (node (ref "C30") (pin "2") (pinfunction "2_2") (pintype "passive"))
      (node (ref "C31") (pin "2") (pinfunction "2_2") (pintype "passive"))
      (node (ref "C32") (pin "2") (pinfunction "2_2") (pintype "passive"))
      (node (ref "C33") (pin "2") (pinfunction "2_2") (pintype "passive"))
      (node (ref "C34") (pin "2") (pinfunction "2_2") (pintype "passive"))
      (node (ref "C35") (pin "2") (pinfunction "2_2") (pintype "passive"))
      (node (ref "C36") (pin "2") (pinfunction "2_2") (pintype "passive"))
      (node (ref "C37") (pin "2") (pinfunction "2_2") (pintype "passive"))
      (node (ref "C38") (pin "2") (pinfunction "2_2") (pintype "passive"))
      (node (ref "C39") (pin "2") (pinfunction "2_2") (pintype "passive"))
      (node (ref "C4") (pin "2") (pinfunction "2_2") (pintype "passive"))
      (node (ref "C40") (pin "2") (pinfunction "2_2") (pintype "passive"))
      (node (ref "C41") (pin "2") (pinfunction "2_2") (pintype "passive"))
      (node (ref "C42") (pin "2") (pinfunction "2_2") (pintype "passive"))
      (node (ref "C43") (pin "1") (pinfunction "1_1") (pintype "passive"))
      (node (ref "C44") (pin "1") (pinfunction "1_1") (pintype "passive"))
      (node (ref "C45") (pin "1") (pinfunction "1_1") (pintype "passive"))
      (node (ref "C46") (pin "1") (pinfunction "1_1") (pintype "passive"))
      (node (ref "C47") (pin "1") (pinfunction "1_1") (pintype "passive"))
      (node (ref "C5") (pin "2") (pinfunction "2_2") (pintype "passive"))
      (node (ref "C58") (pin "2") (pinfunction "2_2") (pintype "passive"))
      (node (ref "C59") (pin "2") (pinfunction "2_2") (pintype "passive"))
      (node (ref "C6") (pin "2") (pinfunction "2_2") (pintype "passive"))
      (node (ref "C60") (pin "2") (pinfunction "2_2") (pintype "passive"))
      (node (ref "C61") (pin "2") (pinfunction "2_2") (pintype "passive"))
      (node (ref "C62") (pin "2") (pinfunction "2_2") (pintype "passive"))
      (node (ref "C63") (pin "2") (pinfunction "2_2") (pintype "passive"))
      (node (ref "C66") (pin "2") (pinfunction "2_2") (pintype "passive"))
      (node (ref "C67") (pin "1") (pinfunction "1_1") (pintype "passive"))
      (node (ref "C68") (pin "2") (pinfunction "2_2") (pintype "passive"))
      (node (ref "C69") (pin "2") (pinfunction "2_2") (pintype "passive"))
      (node (ref "C7") (pin "2") (pinfunction "2_2") (pintype "passive"))
      (node (ref "C70") (pin "2") (pinfunction "2_2") (pintype "passive"))
      (node (ref "C71") (pin "2") (pinfunction "2_2") (pintype "passive"))
      (node (ref "C72") (pin "2") (pinfunction "2_2") (pintype "passive"))
      (node (ref "C73") (pin "2") (pinfunction "2_2") (pintype "passive"))
      (node (ref "C74") (pin "2") (pinfunction "2_2") (pintype "passive"))
      (node (ref "C75") (pin "2") (pinfunction "2_2") (pintype "passive"))
      (node (ref "C76") (pin "2") (pinfunction "2_2") (pintype "passive"))
      (node (ref "C77") (pin "2") (pinfunction "2_2") (pintype "passive"))
      (node (ref "C78") (pin "2") (pinfunction "2_2") (pintype "passive"))
      (node (ref "C79") (pin "2") (pinfunction "2_2") (pintype "passive"))
      (node (ref "C8") (pin "2") (pinfunction "2_2") (pintype "passive"))
      (node (ref "C80") (pin "2") (pinfunction "2_2") (pintype "passive"))
      (node (ref "C81") (pin "2") (pinfunction "2_2") (pintype "passive"))
      (node (ref "C82") (pin "2") (pinfunction "2_2") (pintype "passive"))
      (node (ref "C83") (pin "2") (pinfunction "2_2") (pintype "passive"))
      (node (ref "C84") (pin "2") (pinfunction "2_2") (pintype "passive"))
      (node (ref "C85") (pin "2") (pinfunction "2_2") (pintype "passive"))
      (node (ref "C86") (pin "2") (pinfunction "2_2") (pintype "passive"))
      (node (ref "C87") (pin "2") (pinfunction "2_2") (pintype "passive"))
      (node (ref "C88") (pin "2") (pinfunction "2_2") (pintype "passive"))
      (node (ref "C89") (pin "2") (pinfunction "2_2") (pintype "passive"))
      (node (ref "C9") (pin "2") (pinfunction "2_2") (pintype "passive"))
      (node (ref "C90") (pin "2") (pinfunction "2_2") (pintype "passive"))
      (node (ref "C91") (pin "2") (pinfunction "2_2") (pintype "passive"))
      (node (ref "C92") (pin "2") (pinfunction "2_2") (pintype "passive"))
      (node (ref "C93") (pin "2") (pinfunction "2_2") (pintype "passive"))
      (node (ref "C94") (pin "2") (pinfunction "2_2") (pintype "passive"))
      (node (ref "C95") (pin "2") (pinfunction "2_2") (pintype "passive"))
      (node (ref "C96") (pin "2") (pinfunction "2_2") (pintype "passive"))
      (node (ref "C97") (pin "2") (pinfunction "2_2") (pintype "passive"))
      (node (ref "C98") (pin "2") (pinfunction "2_2") (pintype "passive"))
      (node (ref "C99") (pin "2") (pinfunction "2_2") (pintype "passive"))
      (node (ref "JP2") (pin "1") (pinfunction "1_1") (pintype "bidirectional"))
      (node (ref "JP6") (pin "1") (pinfunction "1_1") (pintype "bidirectional"))
      (node (ref "JP7") (pin "1") (pinfunction "1_1") (pintype "passive"))
      (node (ref "Q1") (pin "2") (pinfunction "S_2") (pintype "passive"))
      (node (ref "Q2") (pin "2") (pinfunction "S_2") (pintype "passive"))
      (node (ref "Q3") (pin "2") (pinfunction "S_2") (pintype "passive"))
      (node (ref "Q4") (pin "2") (pinfunction "S_2") (pintype "passive"))
      (node (ref "Q5") (pin "2") (pinfunction "S_2") (pintype "passive"))
      (node (ref "Q6") (pin "2") (pinfunction "S_2") (pintype "passive"))
      (node (ref "R1") (pin "1") (pinfunction "1_1") (pintype "passive"))
      (node (ref "R10") (pin "1") (pinfunction "1_1") (pintype "passive"))
      (node (ref "R14") (pin "1") (pinfunction "1_1") (pintype "passive"))
      (node (ref "R18") (pin "1") (pinfunction "1_1") (pintype "passive"))
      (node (ref "R22") (pin "1") (pinfunction "1_1") (pintype "passive"))
      (node (ref "R6") (pin "1") (pinfunction "1_1") (pintype "passive"))
    )
    (net (code "2") (name "Net-(C10-Pad1)") (class "Default")
      (node (ref "C10") (pin "1") (pinfunction "1_1") (pintype "passive"))
      (node (ref "K4") (pin "S0") (pinfunction "S_S0") (pintype "passive"))
      (node (ref "K4") (pin "S1") (pinfunction "S_S1") (pintype "passive"))
      (node (ref "L13") (pin "1") (pinfunction "1_1") (pintype "passive"))
    )
    (net (code "3") (name "Net-(C10-Pad2)") (class "Default")
      (node (ref "C10") (pin "2") (pinfunction "2_2") (pintype "passive"))
      (node (ref "C31") (pin "1") (pinfunction "1_1") (pintype "passive"))
    )
    (net (code "4") (name "Net-(C11-Pad1)") (class "Default")
      (node (ref "C11") (pin "1") (pinfunction "1_1") (pintype "passive"))
      (node (ref "L13") (pin "2") (pinfunction "2_2") (pintype "passive"))
      (node (ref "L14") (pin "1") (pinfunction "1_1") (pintype "passive"))
    )
    (net (code "5") (name "Net-(C11-Pad2)") (class "Default")
      (node (ref "C11") (pin "2") (pinfunction "2_2") (pintype "passive"))
      (node (ref "C32") (pin "1") (pinfunction "1_1") (pintype "passive"))
    )
    (net (code "6") (name "Net-(C12-Pad1)") (class "Default")
      (node (ref "C12") (pin "1") (pinfunction "1_1") (pintype "passive"))
      (node (ref "L14") (pin "2") (pinfunction "2_2") (pintype "passive"))
      (node (ref "L15") (pin "1") (pinfunction "1_1") (pintype "passive"))
    )
    (net (code "7") (name "Net-(C12-Pad2)") (class "Default")
      (node (ref "C12") (pin "2") (pinfunction "2_2") (pintype "passive"))
      (node (ref "C33") (pin "1") (pinfunction "1_1") (pintype "passive"))
    )
    (net (code "8") (name "Net-(C13-Pad1)") (class "Default")
      (node (ref "C13") (pin "1") (pinfunction "1_1") (pintype "passive"))
      (node (ref "K9") (pin "S0") (pinfunction "S_S0") (pintype "passive"))
      (node (ref "K9") (pin "S1") (pinfunction "S_S1") (pintype "passive"))
      (node (ref "L15") (pin "2") (pinfunction "2_2") (pintype "passive"))
    )
    (net (code "9") (name "Net-(C13-Pad2)") (class "Default")
      (node (ref "C13") (pin "2") (pinfunction "2_2") (pintype "passive"))
      (node (ref "C34") (pin "1") (pinfunction "1_1") (pintype "passive"))
    )
    (net (code "10") (name "Net-(C14-Pad1)") (class "Default")
      (node (ref "C14") (pin "1") (pinfunction "1_1") (pintype "passive"))
      (node (ref "K5") (pin "S0") (pinfunction "S_S0") (pintype "passive"))
      (node (ref "K5") (pin "S1") (pinfunction "S_S1") (pintype "passive"))
      (node (ref "L16") (pin "1") (pinfunction "1_1") (pintype "passive"))
    )
    (net (code "11") (name "Net-(C14-Pad2)") (class "Default")
      (node (ref "C14") (pin "2") (pinfunction "2_2") (pintype "passive"))
      (node (ref "C35") (pin "1") (pinfunction "1_1") (pintype "passive"))
    )
    (net (code "12") (name "Net-(C15-Pad1)") (class "Default")
      (node (ref "C15") (pin "1") (pinfunction "1_1") (pintype "passive"))
      (node (ref "L16") (pin "2") (pinfunction "2_2") (pintype "passive"))
      (node (ref "L17") (pin "1") (pinfunction "1_1") (pintype "passive"))
    )
    (net (code "13") (name "Net-(C15-Pad2)") (class "Default")
      (node (ref "C15") (pin "2") (pinfunction "2_2") (pintype "passive"))
      (node (ref "C36") (pin "1") (pinfunction "1_1") (pintype "passive"))
    )
    (net (code "14") (name "Net-(C16-Pad1)") (class "Default")
      (node (ref "C16") (pin "1") (pinfunction "1_1") (pintype "passive"))
      (node (ref "L17") (pin "2") (pinfunction "2_2") (pintype "passive"))
      (node (ref "L18") (pin "1") (pinfunction "1_1") (pintype "passive"))
    )
    (net (code "15") (name "Net-(C16-Pad2)") (class "Default")
      (node (ref "C16") (pin "2") (pinfunction "2_2") (pintype "passive"))
      (node (ref "C37") (pin "1") (pinfunction "1_1") (pintype "passive"))
    )
    (net (code "16") (name "Net-(C17-Pad1)") (class "Default")
      (node (ref "C17") (pin "1") (pinfunction "1_1") (pintype "passive"))
      (node (ref "K10") (pin "S0") (pinfunction "S_S0") (pintype "passive"))
      (node (ref "K10") (pin "S1") (pinfunction "S_S1") (pintype "passive"))
      (node (ref "L18") (pin "2") (pinfunction "2_2") (pintype "passive"))
    )
    (net (code "17") (name "Net-(C17-Pad2)") (class "Default")
      (node (ref "C17") (pin "2") (pinfunction "2_2") (pintype "passive"))
      (node (ref "C38") (pin "1") (pinfunction "1_1") (pintype "passive"))
    )
    (net (code "18") (name "Net-(C18-Pad1)") (class "Default")
      (node (ref "C18") (pin "1") (pinfunction "1_1") (pintype "passive"))
      (node (ref "K5") (pin "O0") (pinfunction "O_O0") (pintype "passive"))
      (node (ref "K5") (pin "O1") (pinfunction "O_O1") (pintype "passive"))
      (node (ref "L20") (pin "1") (pinfunction "1_1") (pintype "passive"))
    )
    (net (code "19") (name "Net-(C18-Pad2)") (class "Default")
      (node (ref "C18") (pin "2") (pinfunction "2_2") (pintype "passive"))
      (node (ref "C39") (pin "1") (pinfunction "1_1") (pintype "passive"))
    )
    (net (code "20") (name "Net-(C19-Pad1)") (class "Default")
      (node (ref "C19") (pin "1") (pinfunction "1_1") (pintype "passive"))
      (node (ref "L20") (pin "2") (pinfunction "2_2") (pintype "passive"))
      (node (ref "L21") (pin "1") (pinfunction "1_1") (pintype "passive"))
    )
    (net (code "21") (name "Net-(C19-Pad2)") (class "Default")
      (node (ref "C19") (pin "2") (pinfunction "2_2") (pintype "passive"))
      (node (ref "C40") (pin "1") (pinfunction "1_1") (pintype "passive"))
    )
    (net (code "22") (name "Net-(C20-Pad1)") (class "Default")
      (node (ref "C20") (pin "1") (pinfunction "1_1") (pintype "passive"))
      (node (ref "L21") (pin "2") (pinfunction "2_2") (pintype "passive"))
      (node (ref "L22") (pin "1") (pinfunction "1_1") (pintype "passive"))
    )
    (net (code "23") (name "Net-(C20-Pad2)") (class "Default")
      (node (ref "C20") (pin "2") (pinfunction "2_2") (pintype "passive"))
      (node (ref "C41") (pin "1") (pinfunction "1_1") (pintype "passive"))
    )
    (net (code "24") (name "Net-(C21-Pad1)") (class "Default")
      (node (ref "C21") (pin "1") (pinfunction "1_1") (pintype "passive"))
      (node (ref "K10") (pin "O0") (pinfunction "O_O0") (pintype "passive"))
      (node (ref "K10") (pin "O1") (pinfunction "O_O1") (pintype "passive"))
      (node (ref "L22") (pin "2") (pinfunction "2_2") (pintype "passive"))
    )
    (net (code "25") (name "Net-(C21-Pad2)") (class "Default")
      (node (ref "C21") (pin "2") (pinfunction "2_2") (pintype "passive"))
      (node (ref "C42") (pin "1") (pinfunction "1_1") (pintype "passive"))
    )
    (net (code "26") (name "Net-(C48-Pad1)") (class "Default")
      (node (ref "C48") (pin "1") (pinfunction "1_1") (pintype "passive"))
      (node (ref "D4") (pin "A") (pinfunction "A_A") (pintype "passive"))
      (node (ref "K5") (pin "2") (pinfunction "2_2") (pintype "passive"))
      (node (ref "R9") (pin "2") (pinfunction "2_2") (pintype "passive"))
    )
    (net (code "27") (name "Net-(C48-Pad2)") (class "Default")
      (node (ref "C48") (pin "2") (pinfunction "2_2") (pintype "passive"))
      (node (ref "C49") (pin "2") (pinfunction "2_2") (pintype "passive"))
      (node (ref "C50") (pin "2") (pinfunction "2_2") (pintype "passive"))
      (node (ref "C51") (pin "2") (pinfunction "2_2") (pintype "passive"))
      (node (ref "C52") (pin "2") (pinfunction "2_2") (pintype "passive"))
      (node (ref "C53") (pin "1") (pinfunction "1_1") (pintype "passive"))
      (node (ref "C54") (pin "1") (pinfunction "1_1") (pintype "passive"))
      (node (ref "C55") (pin "1") (pinfunction "1_1") (pintype "passive"))
      (node (ref "C56") (pin "1") (pinfunction "1_1") (pintype "passive"))
      (node (ref "C57") (pin "1") (pinfunction "1_1") (pintype "passive"))
      (node (ref "C64") (pin "1") (pinfunction "1_1") (pintype "passive"))
      (node (ref "C65") (pin "2") (pinfunction "2_2") (pintype "passive"))
      (node (ref "D1") (pin "C") (pinfunction "C_C") (pintype "passive"))
      (node (ref "D10") (pin "C") (pinfunction "C_C") (pintype "passive"))
      (node (ref "D11") (pin "C") (pinfunction "C_C") (pintype "passive"))
      (node (ref "D15") (pin "C") (pinfunction "C_C") (pintype "passive"))
      (node (ref "D2") (pin "C") (pinfunction "C_C") (pintype "passive"))
      (node (ref "D3") (pin "C") (pinfunction "C_C") (pintype "passive"))
      (node (ref "D4") (pin "C") (pinfunction "C_C") (pintype "passive"))
      (node (ref "D5") (pin "C") (pinfunction "C_C") (pintype "passive"))
      (node (ref "D6") (pin "C") (pinfunction "C_C") (pintype "passive"))
      (node (ref "D7") (pin "C") (pinfunction "C_C") (pintype "passive"))
      (node (ref "D8") (pin "C") (pinfunction "C_C") (pintype "passive"))
      (node (ref "D9") (pin "C") (pinfunction "C_C") (pintype "passive"))
      (node (ref "JP3") (pin "1") (pinfunction "1_1") (pintype "bidirectional"))
      (node (ref "K1") (pin "1") (pinfunction "1_1") (pintype "passive"))
      (node (ref "K10") (pin "1") (pinfunction "1_1") (pintype "passive"))
      (node (ref "K11") (pin "1") (pinfunction "1_1") (pintype "passive"))
      (node (ref "K12") (pin "1") (pinfunction "1_1") (pintype "passive"))
      (node (ref "K2") (pin "1") (pinfunction "1_1") (pintype "passive"))
      (node (ref "K3") (pin "1") (pinfunction "1_1") (pintype "passive"))
      (node (ref "K4") (pin "1") (pinfunction "1_1") (pintype "passive"))
      (node (ref "K5") (pin "1") (pinfunction "1_1") (pintype "passive"))
      (node (ref "K6") (pin "1") (pinfunction "1_1") (pintype "passive"))
      (node (ref "K7") (pin "1") (pinfunction "1_1") (pintype "passive"))
      (node (ref "K8") (pin "1") (pinfunction "1_1") (pintype "passive"))
      (node (ref "K9") (pin "1") (pinfunction "1_1") (pintype "passive"))
    )
    (net (code "28") (name "Net-(C49-Pad1)") (class "Default")
      (node (ref "C49") (pin "1") (pinfunction "1_1") (pintype "passive"))
      (node (ref "D3") (pin "A") (pinfunction "A_A") (pintype "passive"))
      (node (ref "K4") (pin "2") (pinfunction "2_2") (pintype "passive"))
      (node (ref "R13") (pin "2") (pinfunction "2_2") (pintype "passive"))
    )
    (net (code "29") (name "Net-(C50-Pad1)") (class "Default")
      (node (ref "C50") (pin "1") (pinfunction "1_1") (pintype "passive"))
      (node (ref "D2") (pin "A") (pinfunction "A_A") (pintype "passive"))
      (node (ref "K2") (pin "2") (pinfunction "2_2") (pintype "passive"))
      (node (ref "R5") (pin "2") (pinfunction "2_2") (pintype "passive"))
    )
    (net (code "30") (name "Net-(C51-Pad1)") (class "Default")
      (node (ref "C51") (pin "1") (pinfunction "1_1") (pintype "passive"))
      (node (ref "D15") (pin "A") (pinfunction "A_A") (pintype "passive"))
      (node (ref "K3") (pin "2") (pinfunction "2_2") (pintype "passive"))
      (node (ref "R2") (pin "2") (pinfunction "2_2") (pintype "passive"))
    )
    (net (code "31") (name "Net-(C52-Pad1)") (class "Default")
      (node (ref "C52") (pin "1") (pinfunction "1_1") (pintype "passive"))
      (node (ref "D1") (pin "A") (pinfunction "A_A") (pintype "passive"))
      (node (ref "K1") (pin "2") (pinfunction "2_2") (pintype "passive"))
      (node (ref "R17") (pin "2") (pinfunction "2_2") (pintype "passive"))
    )
    (net (code "32") (name "Net-(C53-Pad2)") (class "Default")
      (node (ref "C53") (pin "2") (pinfunction "2_2") (pintype "passive"))
      (node (ref "D9") (pin "A") (pinfunction "A_A") (pintype "passive"))
      (node (ref "K10") (pin "2") (pinfunction "2_2") (pintype "passive"))
      (node (ref "R12") (pin "2") (pinfunction "2_2") (pintype "passive"))
    )
    (net (code "33") (name "Net-(C54-Pad2)") (class "Default")
      (node (ref "C54") (pin "2") (pinfunction "2_2") (pintype "passive"))
      (node (ref "D8") (pin "A") (pinfunction "A_A") (pintype "passive"))
      (node (ref "K9") (pin "2") (pinfunction "2_2") (pintype "passive"))
      (node (ref "R16") (pin "2") (pinfunction "2_2") (pintype "passive"))
    )
    (net (code "34") (name "Net-(C55-Pad2)") (class "Default")
      (node (ref "C55") (pin "2") (pinfunction "2_2") (pintype "passive"))
      (node (ref "D7") (pin "A") (pinfunction "A_A") (pintype "passive"))
      (node (ref "K8") (pin "2") (pinfunction "2_2") (pintype "passive"))
      (node (ref "R8") (pin "2") (pinfunction "2_2") (pintype "passive"))
    )
    (net (code "35") (name "Net-(C56-Pad2)") (class "Default")
      (node (ref "C56") (pin "2") (pinfunction "2_2") (pintype "passive"))
      (node (ref "D6") (pin "A") (pinfunction "A_A") (pintype "passive"))
      (node (ref "K7") (pin "2") (pinfunction "2_2") (pintype "passive"))
      (node (ref "R20") (pin "2") (pinfunction "2_2") (pintype "passive"))
    )
    (net (code "36") (name "Net-(C57-Pad2)") (class "Default")
      (node (ref "C57") (pin "2") (pinfunction "2_2") (pintype "passive"))
      (node (ref "D5") (pin "A") (pinfunction "A_A") (pintype "passive"))
      (node (ref "K6") (pin "2") (pinfunction "2_2") (pintype "passive"))
      (node (ref "R4") (pin "2") (pinfunction "2_2") (pintype "passive"))
    )
    (net (code "37") (name "Net-(C64-Pad2)") (class "Default")
      (node (ref "C64") (pin "2") (pinfunction "2_2") (pintype "passive"))
      (node (ref "D10") (pin "A") (pinfunction "A_A") (pintype "passive"))
      (node (ref "K12") (pin "2") (pinfunction "2_2") (pintype "passive"))
      (node (ref "R24") (pin "2") (pinfunction "2_2") (pintype "passive"))
    )
    (net (code "38") (name "Net-(C65-Pad1)") (class "Default")
      (node (ref "C65") (pin "1") (pinfunction "1_1") (pintype "passive"))
      (node (ref "D11") (pin "A") (pinfunction "A_A") (pintype "passive"))
      (node (ref "K11") (pin "2") (pinfunction "2_2") (pintype "passive"))
      (node (ref "R21") (pin "2") (pinfunction "2_2") (pintype "passive"))
    )
    (net (code "39") (name "Net-(C102-Pad1)") (class "Default")
      (node (ref "C102") (pin "1") (pinfunction "1_1") (pintype "passive"))
      (node (ref "C103") (pin "1") (pinfunction "1_1") (pintype "passive"))
      (node (ref "C104") (pin "1") (pinfunction "1_1") (pintype "passive"))
      (node (ref "C105") (pin "1") (pinfunction "1_1") (pintype "passive"))
      (node (ref "C7") (pin "1") (pinfunction "1_1") (pintype "passive"))
      (node (ref "C8") (pin "1") (pinfunction "1_1") (pintype "passive"))
      (node (ref "C9") (pin "1") (pinfunction "1_1") (pintype "passive"))
      (node (ref "CE1") (pin "2") (pinfunction "2_2") (pintype "passive"))
      (node (ref "CE2") (pin "1") (pinfunction "1_1") (pintype "passive"))
      (node (ref "L10") (pin "1") (pinfunction "1_1") (pintype "passive"))
      (node (ref "L7") (pin "2") (pinfunction "2_2") (pintype "passive"))
    )
    (net (code "40") (name "Net-(JP1-Pad1)") (class "Default")
      (node (ref "JP1") (pin "1") (pinfunction "1_1") (pintype "bidirectional"))
      (node (ref "K11") (pin "P0") (pinfunction "P_P0") (pintype "passive"))
      (node (ref "K11") (pin "P1") (pinfunction "P_P1") (pintype "passive"))
    )
    (net (code "41") (name "Net-(JP5-Pad1)") (class "Default")
      (node (ref "JP5") (pin "1") (pinfunction "1_1") (pintype "bidirectional"))
      (node (ref "K12") (pin "P0") (pinfunction "P_P0") (pintype "passive"))
      (node (ref "K12") (pin "P1") (pinfunction "P_P1") (pintype "passive"))
    )
    (net (code "42") (name "Net-(JP7-Pad3)") (class "Default")
      (node (ref "JP7") (pin "3") (pinfunction "3_3") (pintype "passive"))
      (node (ref "R3") (pin "2") (pinfunction "2_2") (pintype "passive"))
    )
    (net (code "43") (name "Net-(JP7-Pad4)") (class "Default")
      (node (ref "JP7") (pin "4") (pinfunction "4_4") (pintype "passive"))
      (node (ref "R19") (pin "2") (pinfunction "2_2") (pintype "passive"))
    )
    (net (code "44") (name "Net-(JP7-Pad5)") (class "Default")
      (node (ref "JP7") (pin "5") (pinfunction "5_5") (pintype "passive"))
      (node (ref "R7") (pin "2") (pinfunction "2_2") (pintype "passive"))
    )
    (net (code "45") (name "Net-(JP7-Pad6)") (class "Default")
      (node (ref "JP7") (pin "6") (pinfunction "6_6") (pintype "passive"))
      (node (ref "R15") (pin "2") (pinfunction "2_2") (pintype "passive"))
    )
    (net (code "46") (name "Net-(JP7-Pad7)") (class "Default")
      (node (ref "JP7") (pin "7") (pinfunction "7_7") (pintype "passive"))
      (node (ref "R11") (pin "2") (pinfunction "2_2") (pintype "passive"))
    )
    (net (code "47") (name "Net-(JP7-Pad8)") (class "Default")
      (node (ref "JP7") (pin "8") (pinfunction "8_8") (pintype "passive"))
      (node (ref "R23") (pin "2") (pinfunction "2_2") (pintype "passive"))
    )
    (net (code "48") (name "Net-(K1B-O-PadO0)") (class "Default")
      (node (ref "K1") (pin "O0") (pinfunction "O_O0") (pintype "passive"))
      (node (ref "K1") (pin "O1") (pinfunction "O_O1") (pintype "passive"))
      (node (ref "K2") (pin "P0") (pinfunction "P_P0") (pintype "passive"))
      (node (ref "K2") (pin "P1") (pinfunction "P_P1") (pintype "passive"))
    )
    (net (code "49") (name "Net-(K1B-P-PadP0)") (class "Default")
      (node (ref "K1") (pin "P0") (pinfunction "P_P0") (pintype "passive"))
      (node (ref "K1") (pin "P1") (pinfunction "P_P1") (pintype "passive"))
      (node (ref "K3") (pin "O0") (pinfunction "O_O0") (pintype "passive"))
      (node (ref "K3") (pin "O1") (pinfunction "O_O1") (pintype "passive"))
    )
    (net (code "50") (name "Net-(K2B-O-PadO0)") (class "Default")
      (node (ref "K2") (pin "O0") (pinfunction "O_O0") (pintype "passive"))
      (node (ref "K2") (pin "O1") (pinfunction "O_O1") (pintype "passive"))
      (node (ref "K4") (pin "P0") (pinfunction "P_P0") (pintype "passive"))
      (node (ref "K4") (pin "P1") (pinfunction "P_P1") (pintype "passive"))
    )
    (net (code "51") (name "Net-(K4B-O-PadO0)") (class "Default")
      (node (ref "K4") (pin "O0") (pinfunction "O_O0") (pintype "passive"))
      (node (ref "K4") (pin "O1") (pinfunction "O_O1") (pintype "passive"))
      (node (ref "K5") (pin "P0") (pinfunction "P_P0") (pintype "passive"))
      (node (ref "K5") (pin "P1") (pinfunction "P_P1") (pintype "passive"))
    )
    (net (code "52") (name "Net-(K6B-O-PadO0)") (class "Default")
      (node (ref "K6") (pin "O0") (pinfunction "O_O0") (pintype "passive"))
      (node (ref "K6") (pin "O1") (pinfunction "O_O1") (pintype "passive"))
      (node (ref "K7") (pin "P0") (pinfunction "P_P0") (pintype "passive"))
      (node (ref "K7") (pin "P1") (pinfunction "P_P1") (pintype "passive"))
    )
    (net (code "53") (name "Net-(K7B-O-PadO0)") (class "Default")
      (node (ref "K7") (pin "O0") (pinfunction "O_O0") (pintype "passive"))
      (node (ref "K7") (pin "O1") (pinfunction "O_O1") (pintype "passive"))
      (node (ref "K8") (pin "P0") (pinfunction "P_P0") (pintype "passive"))
      (node (ref "K8") (pin "P1") (pinfunction "P_P1") (pintype "passive"))
    )
    (net (code "54") (name "Net-(K8B-O-PadO0)") (class "Default")
      (node (ref "K8") (pin "O0") (pinfunction "O_O0") (pintype "passive"))
      (node (ref "K8") (pin "O1") (pinfunction "O_O1") (pintype "passive"))
      (node (ref "K9") (pin "P0") (pinfunction "P_P0") (pintype "passive"))
      (node (ref "K9") (pin "P1") (pinfunction "P_P1") (pintype "passive"))
    )
    (net (code "55") (name "Net-(K10B-P-PadP0)") (class "Default")
      (node (ref "K10") (pin "P0") (pinfunction "P_P0") (pintype "passive"))
      (node (ref "K10") (pin "P1") (pinfunction "P_P1") (pintype "passive"))
      (node (ref "K9") (pin "O0") (pinfunction "O_O0") (pintype "passive"))
      (node (ref "K9") (pin "O1") (pinfunction "O_O1") (pintype "passive"))
    )
    (net (code "56") (name "Net-(K11B-O-PadO0)") (class "Default")
      (node (ref "K11") (pin "O0") (pinfunction "O_O0") (pintype "passive"))
      (node (ref "K11") (pin "O1") (pinfunction "O_O1") (pintype "passive"))
      (node (ref "K3") (pin "P0") (pinfunction "P_P0") (pintype "passive"))
      (node (ref "K3") (pin "P1") (pinfunction "P_P1") (pintype "passive"))
    )
    (net (code "57") (name "Net-(K12B-O-PadO0)") (class "Default")
      (node (ref "K12") (pin "O0") (pinfunction "O_O0") (pintype "passive"))
      (node (ref "K12") (pin "O1") (pinfunction "O_O1") (pintype "passive"))
      (node (ref "K6") (pin "P0") (pinfunction "P_P0") (pintype "passive"))
      (node (ref "K6") (pin "P1") (pinfunction "P_P1") (pintype "passive"))
    )
    (net (code "58") (name "Net-(L1-1)") (class "Default")
      (node (ref "K3") (pin "S0") (pinfunction "S_S0") (pintype "passive"))
      (node (ref "K3") (pin "S1") (pinfunction "S_S1") (pintype "passive"))
      (node (ref "L1") (pin "P$1") (pinfunction "1_P$1") (pintype "passive"))
    )
    (net (code "59") (name "Net-(L1-2)") (class "Default")
      (node (ref "C69") (pin "1") (pinfunction "1_1") (pintype "passive"))
      (node (ref "C70") (pin "1") (pinfunction "1_1") (pintype "passive"))
      (node (ref "C71") (pin "1") (pinfunction "1_1") (pintype "passive"))
      (node (ref "C72") (pin "1") (pinfunction "1_1") (pintype "passive"))
      (node (ref "C73") (pin "1") (pinfunction "1_1") (pintype "passive"))
      (node (ref "C74") (pin "1") (pinfunction "1_1") (pintype "passive"))
      (node (ref "L1") (pin "P$2") (pinfunction "2_P$2") (pintype "passive"))
      (node (ref "L2") (pin "P$1") (pinfunction "1_P$1") (pintype "passive"))
    )
    (net (code "60") (name "Net-(L2-2)") (class "Default")
      (node (ref "C1") (pin "1") (pinfunction "1_1") (pintype "passive"))
      (node (ref "C2") (pin "1") (pinfunction "1_1") (pintype "passive"))
      (node (ref "C27") (pin "1") (pinfunction "1_1") (pintype "passive"))
      (node (ref "C28") (pin "1") (pinfunction "1_1") (pintype "passive"))
      (node (ref "C3") (pin "1") (pinfunction "1_1") (pintype "passive"))
      (node (ref "C60") (pin "1") (pinfunction "1_1") (pintype "passive"))
      (node (ref "C61") (pin "1") (pinfunction "1_1") (pintype "passive"))
      (node (ref "L2") (pin "P$2") (pinfunction "2_P$2") (pintype "passive"))
      (node (ref "L3") (pin "P$1") (pinfunction "1_P$1") (pintype "passive"))
    )
    (net (code "61") (name "Net-(L4-1)") (class "Default")
      (node (ref "C112") (pin "1") (pinfunction "1_1") (pintype "passive"))
      (node (ref "C113") (pin "1") (pinfunction "1_1") (pintype "passive"))
      (node (ref "C114") (pin "1") (pinfunction "1_1") (pintype "passive"))
      (node (ref "C115") (pin "1") (pinfunction "1_1") (pintype "passive"))
      (node (ref "C116") (pin "1") (pinfunction "1_1") (pintype "passive"))
      (node (ref "C117") (pin "1") (pinfunction "1_1") (pintype "passive"))
      (node (ref "CE2") (pin "2") (pinfunction "2_2") (pintype "passive"))
      (node (ref "L10") (pin "2") (pinfunction "2_2") (pintype "passive"))
      (node (ref "L4") (pin "P$1") (pinfunction "1_P$1") (pintype "passive"))
    )
    (net (code "62") (name "Net-(L4-2)") (class "Default")
      (node (ref "K8") (pin "S0") (pinfunction "S_S0") (pintype "passive"))
      (node (ref "K8") (pin "S1") (pinfunction "S_S1") (pintype "passive"))
      (node (ref "L4") (pin "P$2") (pinfunction "2_P$2") (pintype "passive"))
    )
    (net (code "63") (name "Net-(L5-1)") (class "Default")
      (node (ref "K1") (pin "S0") (pinfunction "S_S0") (pintype "passive"))
      (node (ref "K1") (pin "S1") (pinfunction "S_S1") (pintype "passive"))
      (node (ref "L5") (pin "P$1") (pinfunction "1_P$1") (pintype "passive"))
    )
    (net (code "64") (name "Net-(L6-2)") (class "Default")
      (node (ref "C100") (pin "1") (pinfunction "1_1") (pintype "passive"))
      (node (ref "C101") (pin "1") (pinfunction "1_1") (pintype "passive"))
      (node (ref "C96") (pin "1") (pinfunction "1_1") (pintype "passive"))
      (node (ref "C97") (pin "1") (pinfunction "1_1") (pintype "passive"))
      (node (ref "C98") (pin "1") (pinfunction "1_1") (pintype "passive"))
      (node (ref "C99") (pin "1") (pinfunction "1_1") (pintype "passive"))
      (node (ref "L6") (pin "P$2") (pinfunction "2_P$2") (pintype "passive"))
      (node (ref "L8") (pin "P$1") (pinfunction "1_P$1") (pintype "passive"))
    )
    (net (code "65") (name "Net-(L8-2)") (class "Default")
      (node (ref "K7") (pin "S0") (pinfunction "S_S0") (pintype "passive"))
      (node (ref "K7") (pin "S1") (pinfunction "S_S1") (pintype "passive"))
      (node (ref "L8") (pin "P$2") (pinfunction "2_P$2") (pintype "passive"))
    )
    (net (code "66") (name "Net-(L9-1)") (class "Default")
      (node (ref "K2") (pin "S0") (pinfunction "S_S0") (pintype "passive"))
      (node (ref "K2") (pin "S1") (pinfunction "S_S1") (pintype "passive"))
      (node (ref "L9") (pin "P$1") (pinfunction "1_P$1") (pintype "passive"))
    )
    (net (code "67") (name "Net-(L9-2)") (class "Default")
      (node (ref "C106") (pin "1") (pinfunction "1_1") (pintype "passive"))
      (node (ref "C107") (pin "1") (pinfunction "1_1") (pintype "passive"))
      (node (ref "C108") (pin "1") (pinfunction "1_1") (pintype "passive"))
      (node (ref "C109") (pin "1") (pinfunction "1_1") (pintype "passive"))
      (node (ref "C110") (pin "1") (pinfunction "1_1") (pintype "passive"))
      (node (ref "C111") (pin "1") (pinfunction "1_1") (pintype "passive"))
      (node (ref "CE1") (pin "1") (pinfunction "1_1") (pintype "passive"))
      (node (ref "L7") (pin "1") (pinfunction "1_1") (pintype "passive"))
      (node (ref "L9") (pin "P$2") (pinfunction "2_P$2") (pintype "passive"))
    )
    (net (code "68") (name "Net-(L11-1)") (class "Default")
      (node (ref "C75") (pin "1") (pinfunction "1_1") (pintype "passive"))
      (node (ref "C76") (pin "1") (pinfunction "1_1") (pintype "passive"))
      (node (ref "C77") (pin "1") (pinfunction "1_1") (pintype "passive"))
      (node (ref "C78") (pin "1") (pinfunction "1_1") (pintype "passive"))
      (node (ref "C79") (pin "1") (pinfunction "1_1") (pintype "passive"))
      (node (ref "C80") (pin "1") (pinfunction "1_1") (pintype "passive"))
      (node (ref "L11") (pin "P$1") (pinfunction "1_P$1") (pintype "passive"))
      (node (ref "L3") (pin "P$2") (pinfunction "2_P$2") (pintype "passive"))
    )
    (net (code "69") (name "Net-(L11-2)") (class "Default")
      (node (ref "K6") (pin "S0") (pinfunction "S_S0") (pintype "passive"))
      (node (ref "K6") (pin "S1") (pinfunction "S_S1") (pintype "passive"))
      (node (ref "L11") (pin "P$2") (pinfunction "2_P$2") (pintype "passive"))
    )
    (net (code "70") (name "Net-(L12-1)") (class "Default")
      (node (ref "C62") (pin "1") (pinfunction "1_1") (pintype "passive"))
      (node (ref "C63") (pin "1") (pinfunction "1_1") (pintype "passive"))
      (node (ref "C66") (pin "1") (pinfunction "1_1") (pintype "passive"))
      (node (ref "C68") (pin "1") (pinfunction "1_1") (pintype "passive"))
      (node (ref "C81") (pin "1") (pinfunction "1_1") (pintype "passive"))
      (node (ref "C82") (pin "1") (pinfunction "1_1") (pintype "passive"))
      (node (ref "L12") (pin "P$1") (pinfunction "1_P$1") (pintype "passive"))
      (node (ref "L24") (pin "P$2") (pinfunction "2_P$2") (pintype "passive"))
    )
    (net (code "71") (name "Net-(L12-2)") (class "Default")
      (node (ref "C22") (pin "1") (pinfunction "1_1") (pintype "passive"))
      (node (ref "C23") (pin "1") (pinfunction "1_1") (pintype "passive"))
      (node (ref "C24") (pin "1") (pinfunction "1_1") (pintype "passive"))
      (node (ref "C25") (pin "1") (pinfunction "1_1") (pintype "passive"))
      (node (ref "C26") (pin "1") (pinfunction "1_1") (pintype "passive"))
      (node (ref "C85") (pin "1") (pinfunction "1_1") (pintype "passive"))
      (node (ref "L12") (pin "P$2") (pinfunction "2_P$2") (pintype "passive"))
      (node (ref "L23") (pin "P$1") (pinfunction "1_P$1") (pintype "passive"))
    )
    (net (code "72") (name "Net-(L19-1)") (class "Default")
      (node (ref "C90") (pin "1") (pinfunction "1_1") (pintype "passive"))
      (node (ref "C91") (pin "1") (pinfunction "1_1") (pintype "passive"))
      (node (ref "C92") (pin "1") (pinfunction "1_1") (pintype "passive"))
      (node (ref "C93") (pin "1") (pinfunction "1_1") (pintype "passive"))
      (node (ref "C94") (pin "1") (pinfunction "1_1") (pintype "passive"))
      (node (ref "C95") (pin "1") (pinfunction "1_1") (pintype "passive"))
      (node (ref "L19") (pin "P$1") (pinfunction "1_P$1") (pintype "passive"))
      (node (ref "L5") (pin "P$2") (pinfunction "2_P$2") (pintype "passive"))
    )
    (net (code "73") (name "Net-(L19-2)") (class "Default")
      (node (ref "C4") (pin "1") (pinfunction "1_1") (pintype "passive"))
      (node (ref "C5") (pin "1") (pinfunction "1_1") (pintype "passive"))
      (node (ref "C6") (pin "1") (pinfunction "1_1") (pintype "passive"))
      (node (ref "C86") (pin "1") (pinfunction "1_1") (pintype "passive"))
      (node (ref "C87") (pin "1") (pinfunction "1_1") (pintype "passive"))
      (node (ref "C88") (pin "1") (pinfunction "1_1") (pintype "passive"))
      (node (ref "C89") (pin "1") (pinfunction "1_1") (pintype "passive"))
      (node (ref "L19") (pin "P$2") (pinfunction "2_P$2") (pintype "passive"))
      (node (ref "L6") (pin "P$1") (pinfunction "1_P$1") (pintype "passive"))
    )
    (net (code "74") (name "Net-(L23-2)") (class "Default")
      (node (ref "C29") (pin "1") (pinfunction "1_1") (pintype "passive"))
      (node (ref "C30") (pin "1") (pinfunction "1_1") (pintype "passive"))
      (node (ref "C58") (pin "1") (pinfunction "1_1") (pintype "passive"))
      (node (ref "C59") (pin "1") (pinfunction "1_1") (pintype "passive"))
      (node (ref "C83") (pin "1") (pinfunction "1_1") (pintype "passive"))
      (node (ref "C84") (pin "1") (pinfunction "1_1") (pintype "passive"))
      (node (ref "L23") (pin "P$2") (pinfunction "2_P$2") (pintype "passive"))
      (node (ref "L25") (pin "P$1") (pinfunction "1_P$1") (pintype "passive"))
    )
    (net (code "75") (name "Net-(L24-1)") (class "Default")
      (node (ref "K11") (pin "S0") (pinfunction "S_S0") (pintype "passive"))
      (node (ref "K11") (pin "S1") (pinfunction "S_S1") (pintype "passive"))
      (node (ref "L24") (pin "P$1") (pinfunction "1_P$1") (pintype "passive"))
    )
    (net (code "76") (name "Net-(L25-2)") (class "Default")
      (node (ref "K12") (pin "S0") (pinfunction "S_S0") (pintype "passive"))
      (node (ref "K12") (pin "S1") (pinfunction "S_S1") (pintype "passive"))
      (node (ref "L25") (pin "P$2") (pinfunction "2_P$2") (pintype "passive"))
    )
    (net (code "77") (name "Net-(Q1-D)") (class "Default")
      (node (ref "Q1") (pin "3") (pinfunction "D_3") (pintype "passive"))
      (node (ref "R5") (pin "1") (pinfunction "1_1") (pintype "passive"))
      (node (ref "R8") (pin "1") (pinfunction "1_1") (pintype "passive"))
    )
    (net (code "78") (name "Net-(Q1-G)") (class "Default")
      (node (ref "C45") (pin "2") (pinfunction "2_2") (pintype "passive"))
      (node (ref "Q1") (pin "1") (pinfunction "G_1") (pintype "passive"))
      (node (ref "R6") (pin "2") (pinfunction "2_2") (pintype "passive"))
      (node (ref "R7") (pin "1") (pinfunction "1_1") (pintype "passive"))
    )
    (net (code "79") (name "Net-(Q2-D)") (class "Default")
      (node (ref "Q2") (pin "3") (pinfunction "D_3") (pintype "passive"))
      (node (ref "R2") (pin "1") (pinfunction "1_1") (pintype "passive"))
      (node (ref "R4") (pin "1") (pinfunction "1_1") (pintype "passive"))
    )
    (net (code "80") (name "Net-(Q2-G)") (class "Default")
      (node (ref "C47") (pin "2") (pinfunction "2_2") (pintype "passive"))
      (node (ref "Q2") (pin "1") (pinfunction "G_1") (pintype "passive"))
      (node (ref "R1") (pin "2") (pinfunction "2_2") (pintype "passive"))
      (node (ref "R3") (pin "1") (pinfunction "1_1") (pintype "passive"))
    )
    (net (code "81") (name "Net-(Q3-D)") (class "Default")
      (node (ref "Q3") (pin "3") (pinfunction "D_3") (pintype "passive"))
      (node (ref "R12") (pin "1") (pinfunction "1_1") (pintype "passive"))
      (node (ref "R9") (pin "1") (pinfunction "1_1") (pintype "passive"))
    )
    (net (code "82") (name "Net-(Q3-G)") (class "Default")
      (node (ref "C43") (pin "2") (pinfunction "2_2") (pintype "passive"))
      (node (ref "Q3") (pin "1") (pinfunction "G_1") (pintype "passive"))
      (node (ref "R10") (pin "2") (pinfunction "2_2") (pintype "passive"))
      (node (ref "R11") (pin "1") (pinfunction "1_1") (pintype "passive"))
    )
    (net (code "83") (name "Net-(Q4-D)") (class "Default")
      (node (ref "Q4") (pin "3") (pinfunction "D_3") (pintype "passive"))
      (node (ref "R13") (pin "1") (pinfunction "1_1") (pintype "passive"))
      (node (ref "R16") (pin "1") (pinfunction "1_1") (pintype "passive"))
    )
    (net (code "84") (name "Net-(Q4-G)") (class "Default")
      (node (ref "C44") (pin "2") (pinfunction "2_2") (pintype "passive"))
      (node (ref "Q4") (pin "1") (pinfunction "G_1") (pintype "passive"))
      (node (ref "R14") (pin "2") (pinfunction "2_2") (pintype "passive"))
      (node (ref "R15") (pin "1") (pinfunction "1_1") (pintype "passive"))
    )
    (net (code "85") (name "Net-(Q5-D)") (class "Default")
      (node (ref "Q5") (pin "3") (pinfunction "D_3") (pintype "passive"))
      (node (ref "R17") (pin "1") (pinfunction "1_1") (pintype "passive"))
      (node (ref "R20") (pin "1") (pinfunction "1_1") (pintype "passive"))
    )
    (net (code "86") (name "Net-(Q5-G)") (class "Default")
      (node (ref "C46") (pin "2") (pinfunction "2_2") (pintype "passive"))
      (node (ref "Q5") (pin "1") (pinfunction "G_1") (pintype "passive"))
      (node (ref "R18") (pin "2") (pinfunction "2_2") (pintype "passive"))
      (node (ref "R19") (pin "1") (pinfunction "1_1") (pintype "passive"))
    )
    (net (code "87") (name "Net-(Q6-D)") (class "Default")
      (node (ref "Q6") (pin "3") (pinfunction "D_3") (pintype "passive"))
      (node (ref "R21") (pin "1") (pinfunction "1_1") (pintype "passive"))
      (node (ref "R24") (pin "1") (pinfunction "1_1") (pintype "passive"))
    )
    (net (code "88") (name "Net-(Q6-G)") (class "Default")
      (node (ref "C67") (pin "2") (pinfunction "2_2") (pintype "passive"))
      (node (ref "Q6") (pin "1") (pinfunction "G_1") (pintype "passive"))
      (node (ref "R22") (pin "2") (pinfunction "2_2") (pintype "passive"))
      (node (ref "R23") (pin "1") (pinfunction "1_1") (pintype "passive"))
    )
    (net (code "89") (name "unconnected-(FID1-PadP$1)") (class "Default")
      (node (ref "FID1") (pin "P$1") (pinfunction "P$1_P$1") (pintype "bidirectional"))
    )
    (net (code "90") (name "unconnected-(FID2-PadP$1)") (class "Default")
      (node (ref "FID2") (pin "P$1") (pinfunction "P$1_P$1") (pintype "bidirectional"))
    )
    (net (code "91") (name "unconnected-(JP7-Pad2)") (class "Default")
      (node (ref "JP7") (pin "2") (pinfunction "2_2") (pintype "passive"))
    )
  )
)
